# mattduino_uno_v7.net
KiCad netlist of a schematic drawn in EAGLE
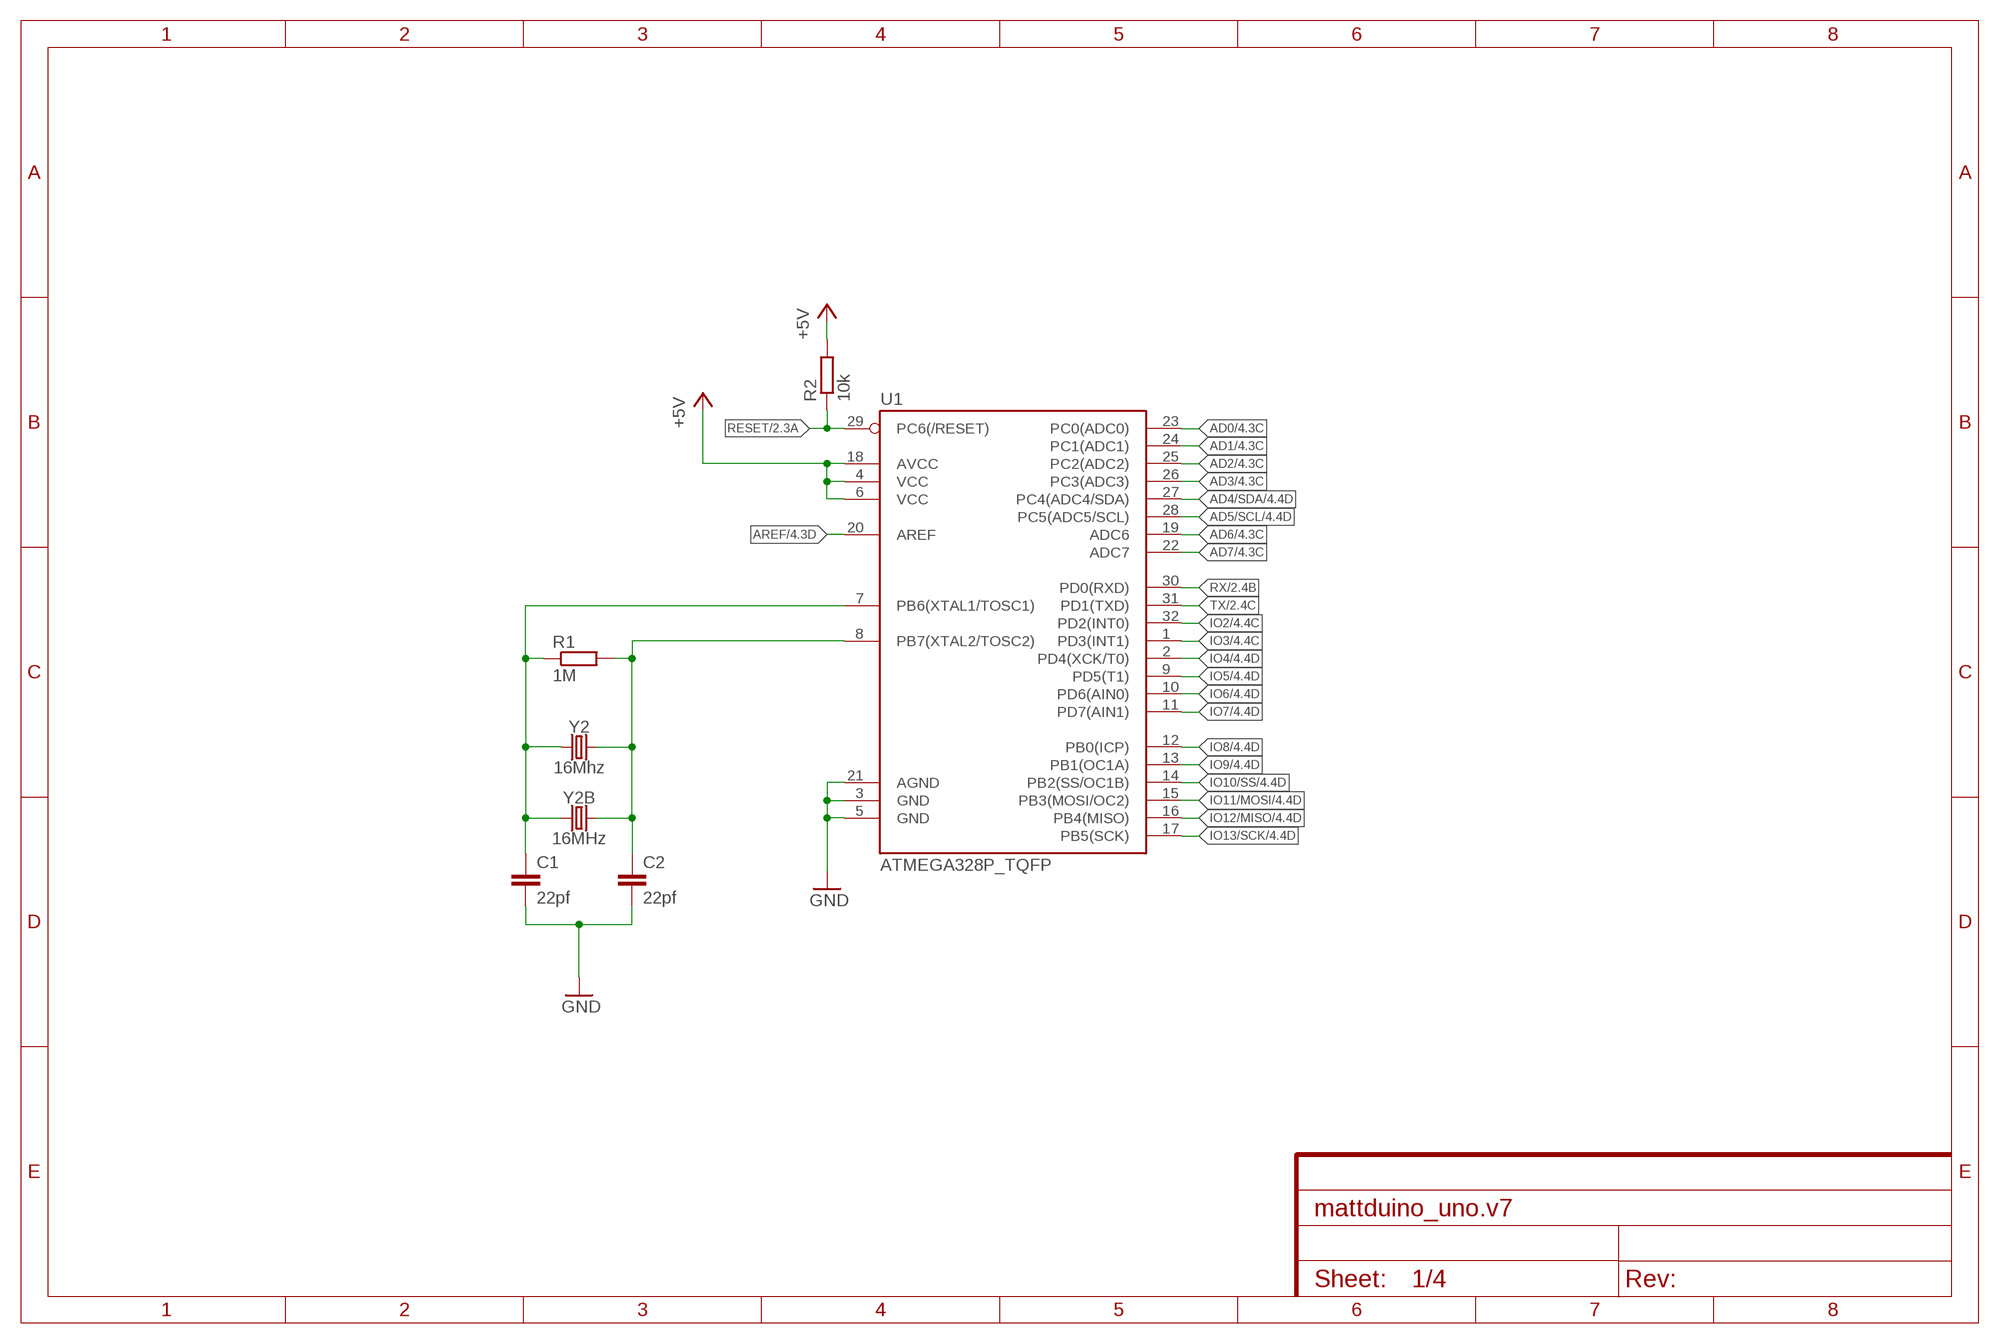
[diagram p0: schematic, sheet 1]
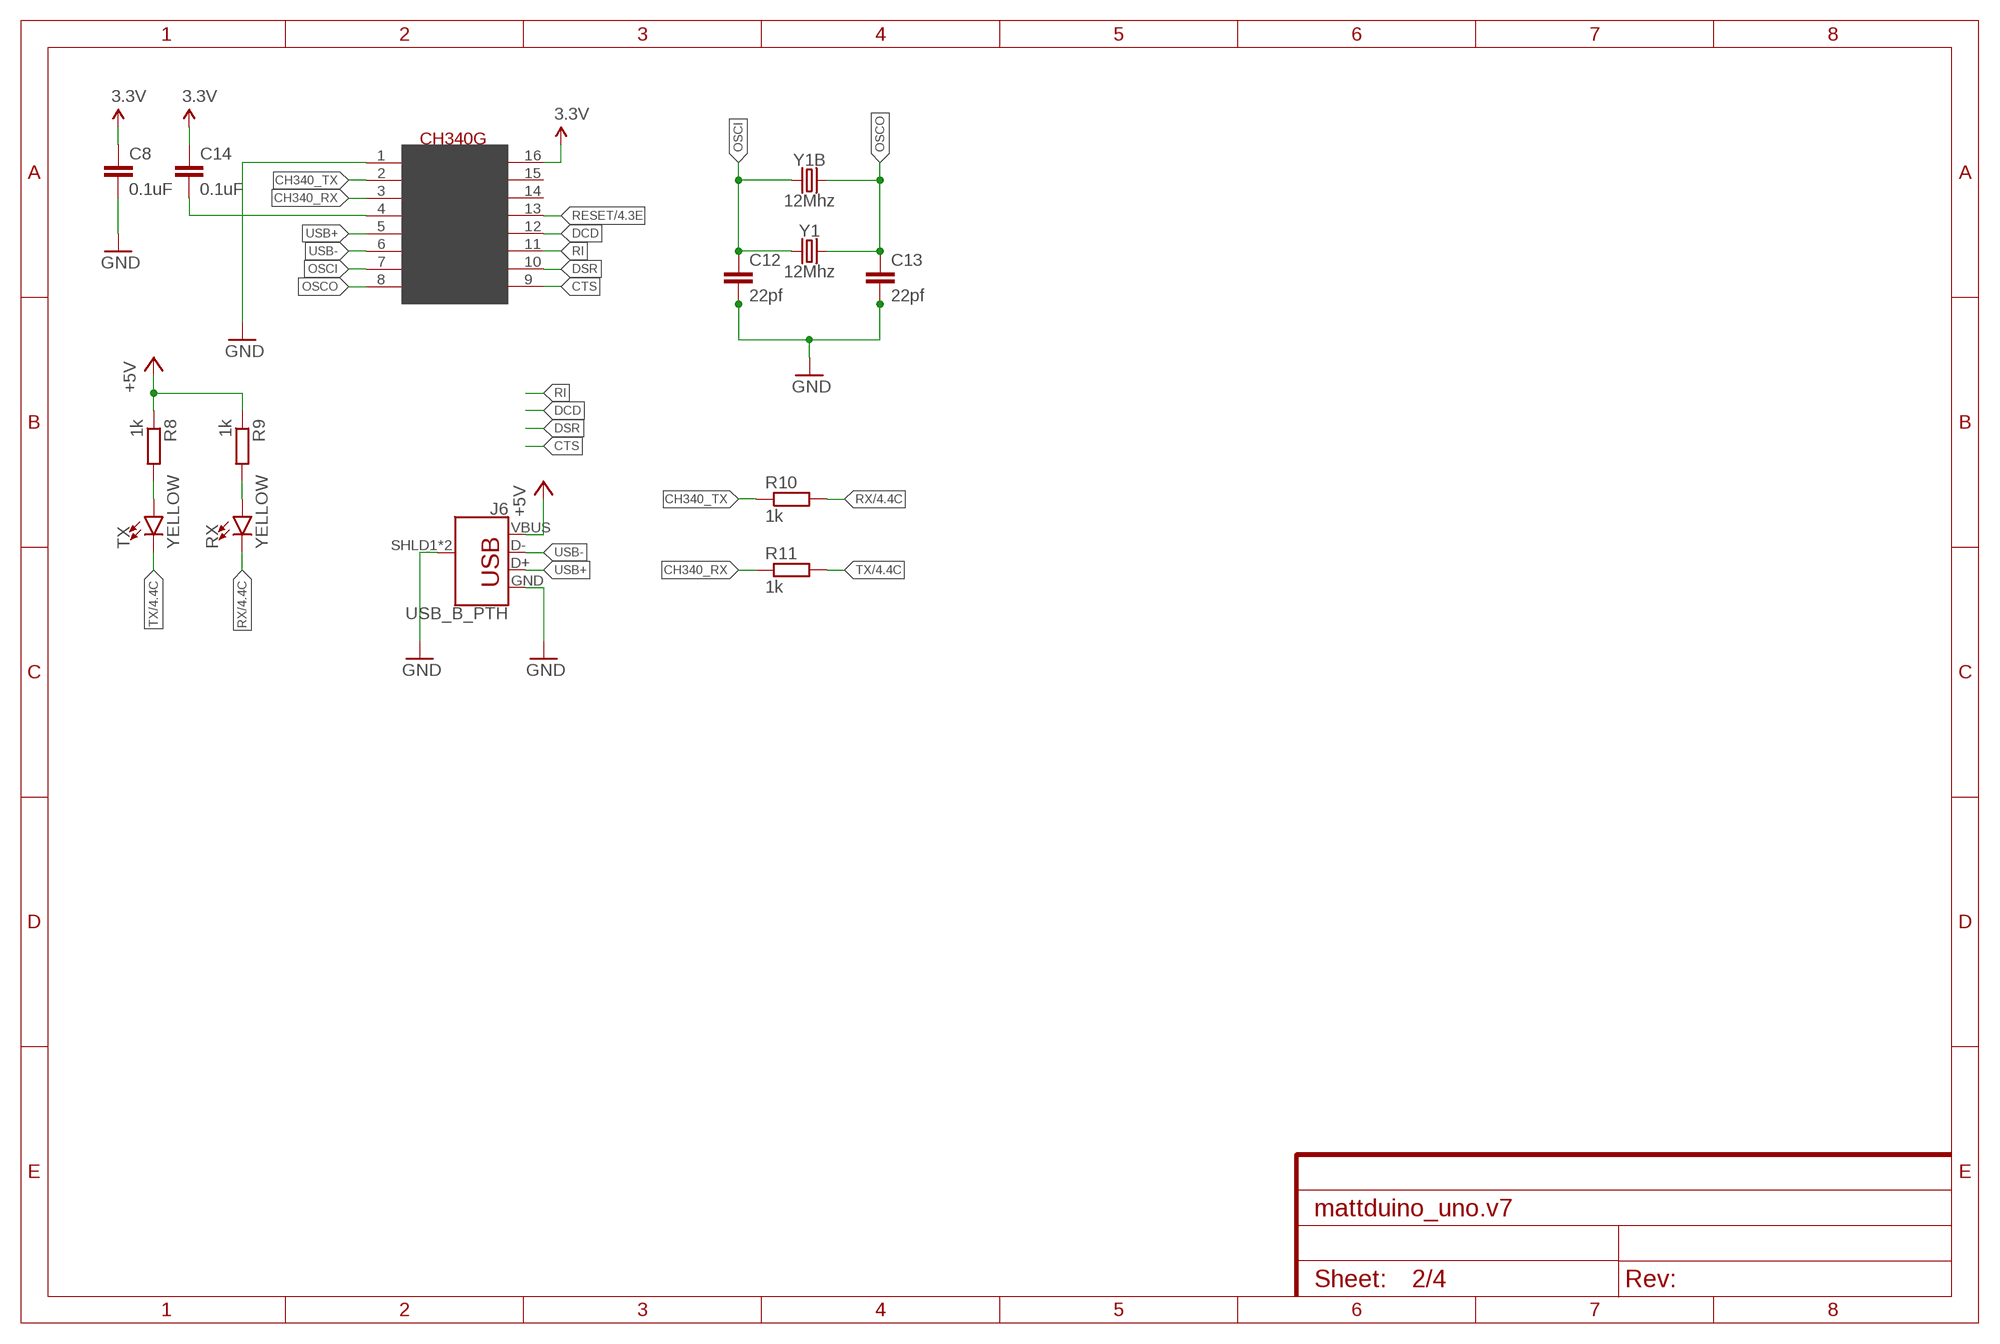
[diagram p1: schematic, sheet 2]
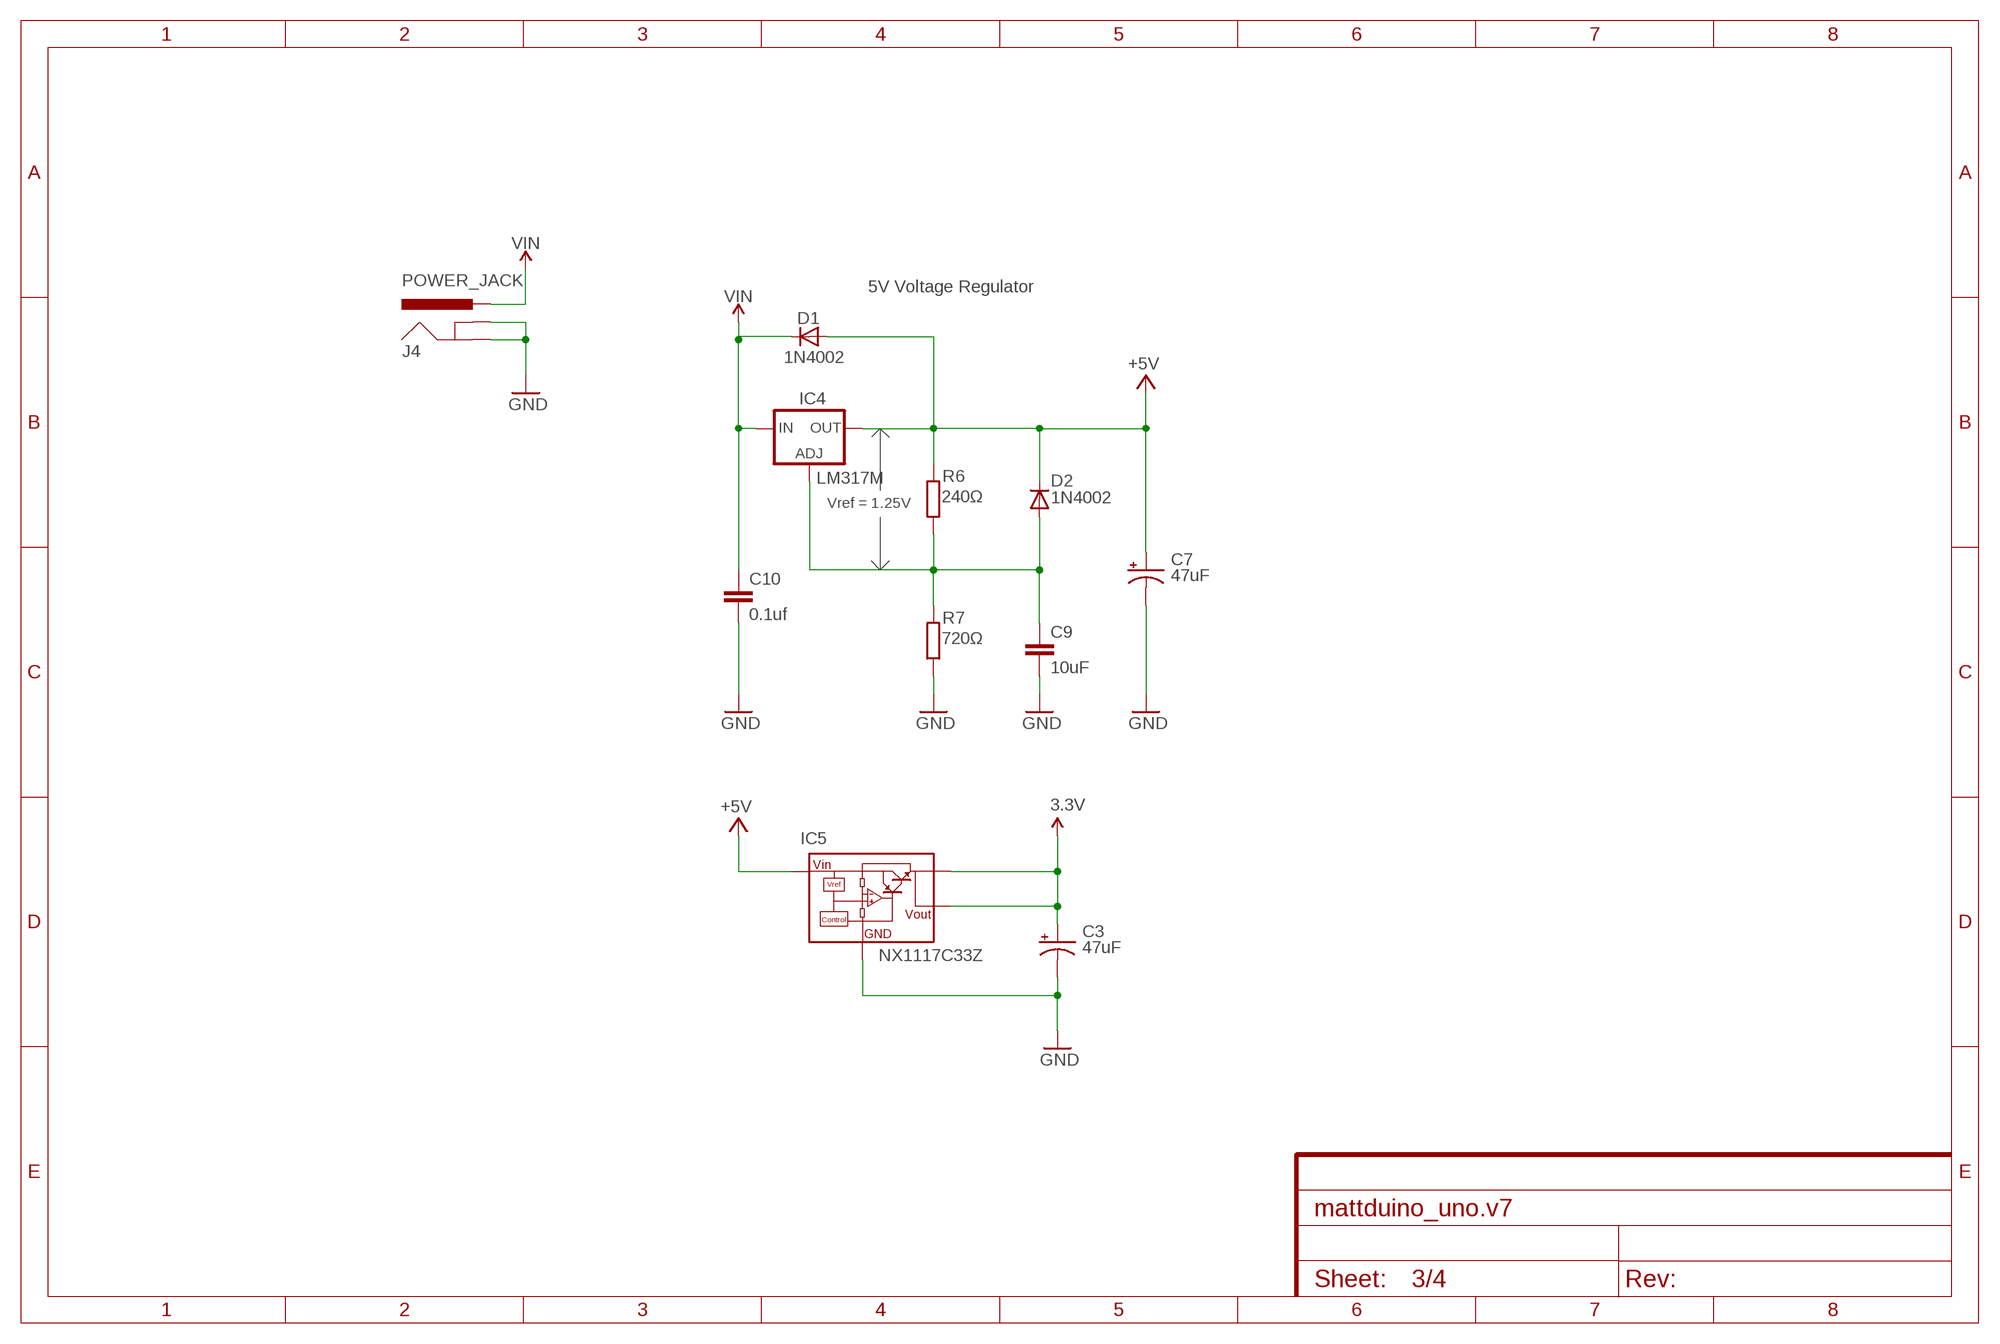
[diagram p2: schematic, sheet 3]
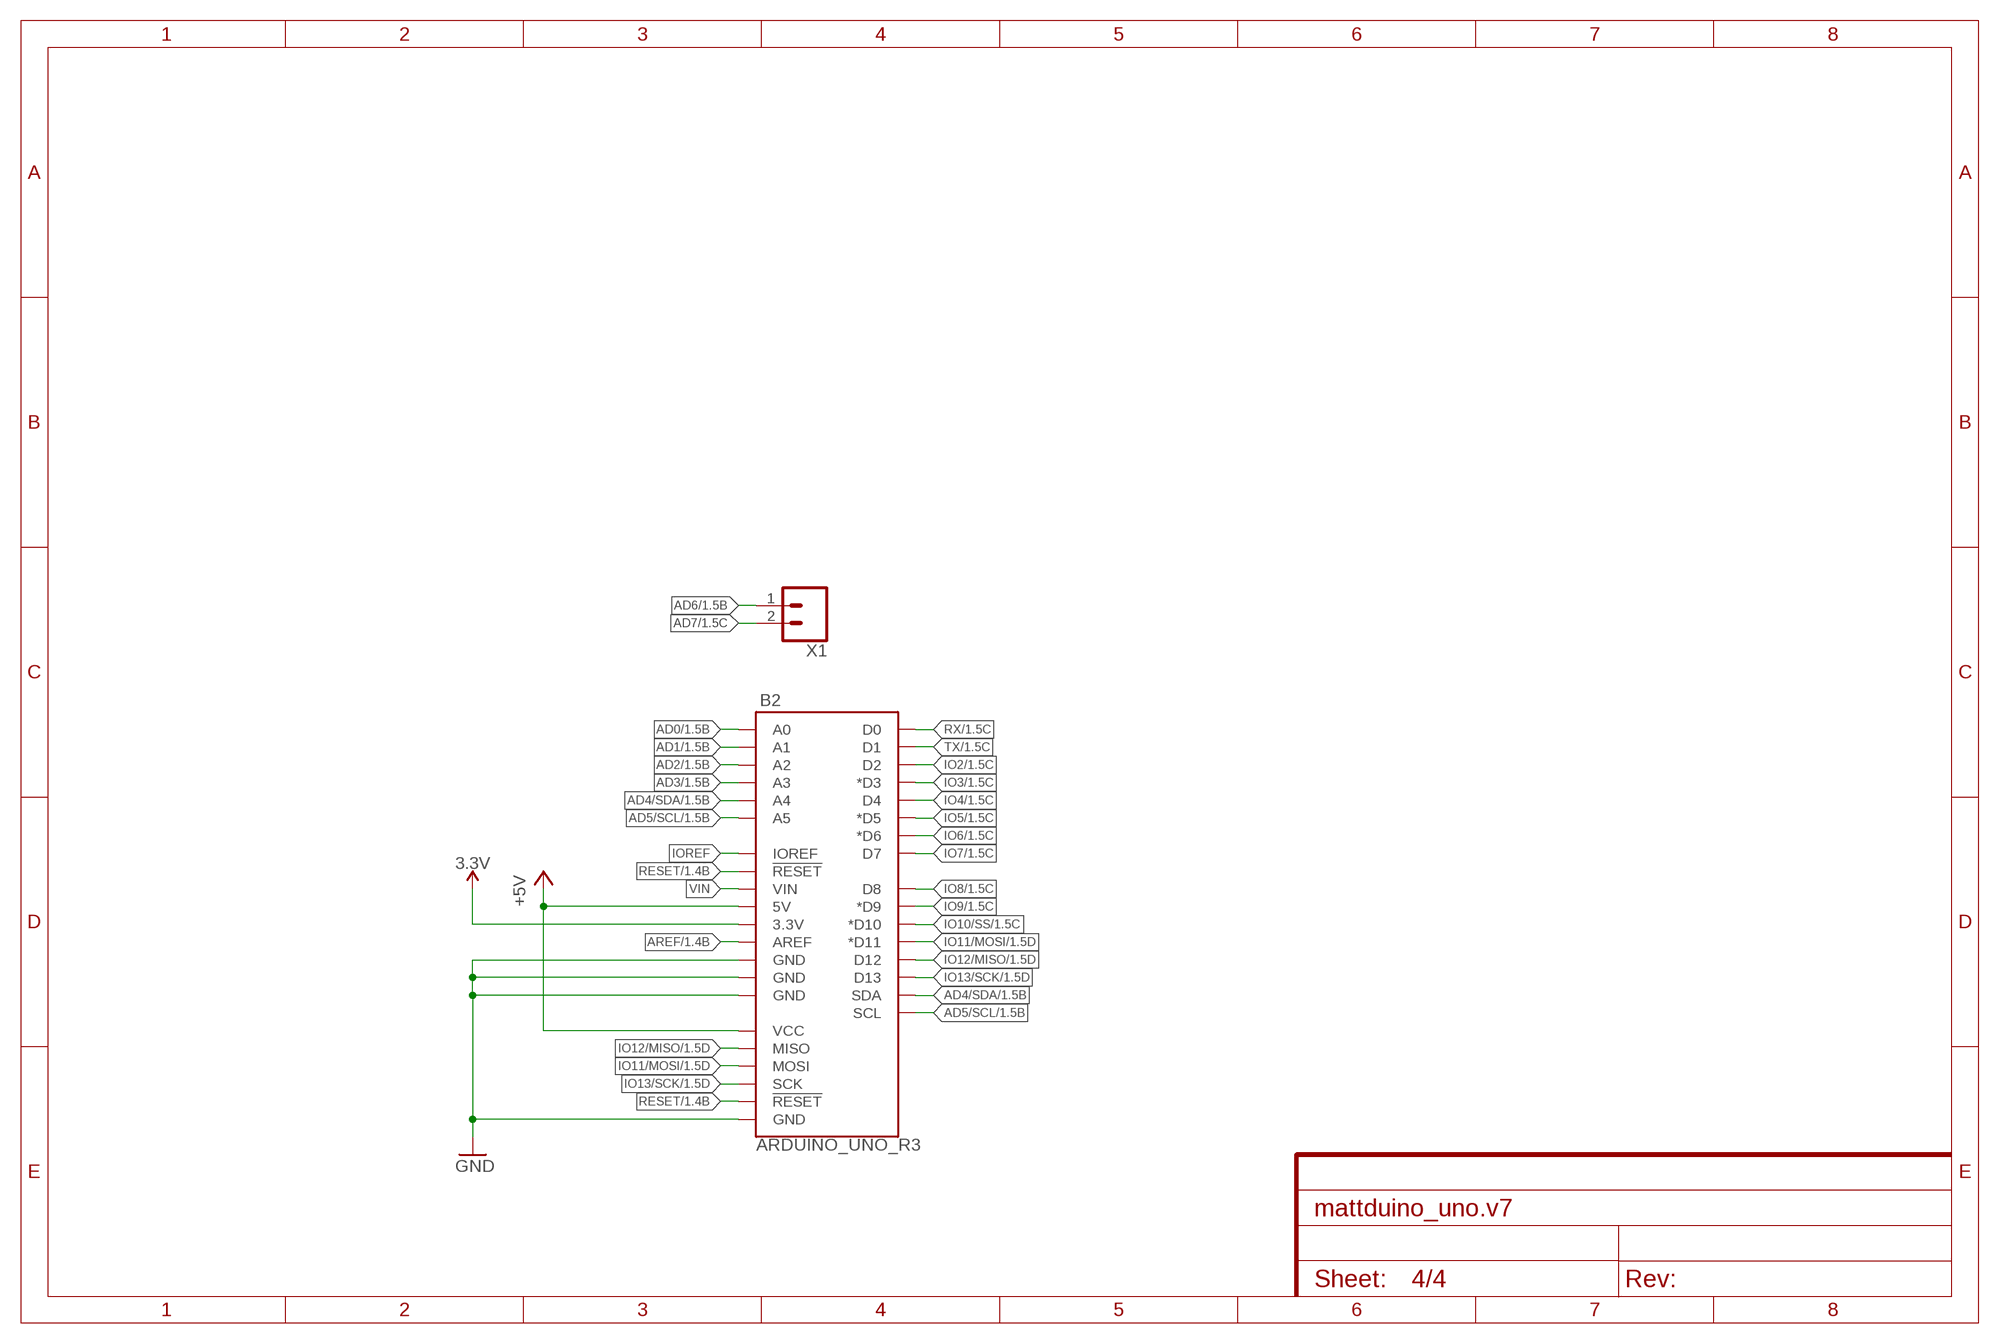
[diagram p3: schematic, sheet 4]

(export (version "E")
  (design (tool "Eeschema 10.0.6"))
  (components
    (comp (ref "C1")
      (value "22pf")
      (footprint "eagle-import:C1206")
      (libsource (lib "eagle-import") (part "C-EUC1206"))
    )
    (comp (ref "C2")
      (value "22pf")
      (footprint "eagle-import:C1206")
      (libsource (lib "eagle-import") (part "C-EUC1206"))
    )
    (comp (ref "R1")
      (value "1M")
      (footprint "eagle-import:R1206")
      (libsource (lib "eagle-import") (part "R-EU_R1206"))
    )
    (comp (ref "R2")
      (value "10k")
      (footprint "eagle-import:R1206")
      (libsource (lib "eagle-import") (part "R-EU_R1206"))
    )
    (comp (ref "U1")
      (value "ATMEGA328P_TQFP")
      (footprint "eagle-import:TQFP32-08")
      (libsource (lib "eagle-import") (part "ATMEGA328P_TQFP"))
    )
    (comp (ref "Y2")
      (value "16Mhz")
      (footprint "eagle-import:HC49UP")
      (libsource (lib "eagle-import") (part "CRYSTAL-8MHZSMD-HC49UP"))
    )
    (comp (ref "Y2B")
      (value "16MHz")
      (footprint "eagle-import:HC49U")
      (libsource (lib "eagle-import") (part "CRYSTALPTH-HC49UV"))
    )
    (comp (ref "C8")
      (value "0.1uF")
      (footprint "eagle-import:C1206")
      (libsource (lib "eagle-import") (part "C-EUC1206"))
    )
    (comp (ref "C12")
      (value "22pf")
      (footprint "eagle-import:C1206")
      (libsource (lib "eagle-import") (part "rcl@1_C-EUC1206"))
    )
    (comp (ref "C13")
      (value "22pf")
      (footprint "eagle-import:C1206")
      (libsource (lib "eagle-import") (part "rcl@1_C-EUC1206"))
    )
    (comp (ref "C14")
      (value "0.1uF")
      (footprint "eagle-import:C1206")
      (libsource (lib "eagle-import") (part "C-EUC1206"))
    )
    (comp (ref "IC3")
      (value "CH340G")
      (footprint "eagle-import:SOIC16")
      (libsource (lib "eagle-import") (part "CH340G"))
    )
    (comp (ref "J6")
      (value "USB_B_PTH")
      (footprint "eagle-import:USB-B-PTH")
      (libsource (lib "eagle-import") (part "USB_B_PTH"))
    )
    (comp (ref "R8")
      (value "1k")
      (footprint "eagle-import:R1206")
      (libsource (lib "eagle-import") (part "R-EU_R1206"))
    )
    (comp (ref "R9")
      (value "1k")
      (footprint "eagle-import:R1206")
      (libsource (lib "eagle-import") (part "R-EU_R1206"))
    )
    (comp (ref "R10")
      (value "1k")
      (footprint "eagle-import:R1206")
      (libsource (lib "eagle-import") (part "R-EU_R1206"))
    )
    (comp (ref "R11")
      (value "1k")
      (footprint "eagle-import:R1206")
      (libsource (lib "eagle-import") (part "R-EU_R1206"))
    )
    (comp (ref "RX")
      (value "YELLOW")
      (footprint "eagle-import:LED-1206")
      (libsource (lib "eagle-import") (part "LED1206"))
    )
    (comp (ref "TX")
      (value "YELLOW")
      (footprint "eagle-import:LED-1206")
      (libsource (lib "eagle-import") (part "LED1206"))
    )
    (comp (ref "Y1")
      (value "12Mhz")
      (footprint "eagle-import:HC49U")
      (libsource (lib "eagle-import") (part "CRYSTALPTH-HC49UV"))
    )
    (comp (ref "Y1B")
      (value "12Mhz")
      (footprint "eagle-import:HC49UP")
      (libsource (lib "eagle-import") (part "CRYSTAL-8MHZSMD-HC49UP"))
    )
    (comp (ref "C3")
      (value "47uF")
      (footprint "eagle-import:PANASONIC_D")
      (libsource (lib "eagle-import") (part "47UF-POLAR-PANASONIC_D-35V-20%"))
    )
    (comp (ref "C7")
      (value "47uF")
      (footprint "eagle-import:PANASONIC_D")
      (libsource (lib "eagle-import") (part "47UF-POLAR-PANASONIC_D-35V-20%"))
    )
    (comp (ref "C9")
      (value "10uF")
      (footprint "eagle-import:C1206")
      (libsource (lib "eagle-import") (part "C-EUC1206"))
    )
    (comp (ref "C10")
      (value "0.1uf")
      (footprint "eagle-import:C1206")
      (libsource (lib "eagle-import") (part "C-EUC1206"))
    )
    (comp (ref "D1")
      (value "1N4002")
      (footprint "eagle-import:SOD-123")
      (libsource (lib "eagle-import") (part "DIODESOD-123"))
    )
    (comp (ref "D2")
      (value "1N4002")
      (footprint "eagle-import:SOD-123")
      (libsource (lib "eagle-import") (part "DIODESOD-123"))
    )
    (comp (ref "IC4")
      (value "LM317MBSTT3")
      (footprint "eagle-import:SOT223")
      (fields (field (name "PARTNUMBER") "LM317M"))
      (libsource (lib "eagle-import") (part "LM317?MBSTT3"))
    )
    (comp (ref "IC5")
      (value "NX1117C33Z")
      (footprint "eagle-import:SOT223")
      (fields (field (name "TOLERANCE") "1.25%") (field (name "VOLTAGE") "5.0V"))
      (libsource (lib "eagle-import") (part "NX1117CZ33"))
    )
    (comp (ref "J4")
      (value "POWER_JACK")
      (footprint "eagle-import:POWER_JACK_PTH")
      (libsource (lib "eagle-import") (part "POWER_JACK"))
    )
    (comp (ref "R6")
      (value "240Ω")
      (footprint "eagle-import:R1206")
      (libsource (lib "eagle-import") (part "R-EU_R1206"))
    )
    (comp (ref "R7")
      (value "720Ω")
      (footprint "eagle-import:R1206")
      (libsource (lib "eagle-import") (part "R-EU_R1206"))
    )
    (comp (ref "B2")
      (value "ARDUINO_UNO_R3")
      (footprint "eagle-import:ARDUINO_R3")
      (libsource (lib "eagle-import") (part "ARDUINO_UNO_R3"))
    )
    (comp (ref "X1")
      (value "CONN_02")
      (footprint "eagle-import:1X02")
      (libsource (lib "eagle-import") (part "CONN_02"))
    )
  )
  (nets
    (net (code "1") (name "+5V") (class "Default")
      (node (ref "B2") (pin "5V") (pinfunction "5V_5V") (pintype "bidirectional"))
      (node (ref "B2") (pin "VCC") (pinfunction "VCC_VCC") (pintype "bidirectional"))
      (node (ref "C7") (pin "+") (pinfunction "+_+") (pintype "passive"))
      (node (ref "D1") (pin "A") (pinfunction "A_A") (pintype "passive"))
      (node (ref "D2") (pin "C") (pinfunction "C_C") (pintype "passive"))
      (node (ref "IC4") (pin "4") (pinfunction "OUT_4") (pintype "passive"))
      (node (ref "IC5") (pin "3") (pinfunction "VIN_3") (pintype "input"))
      (node (ref "J6") (pin "VBUS") (pinfunction "VBUS_VBUS") (pintype "power_in"))
      (node (ref "R2") (pin "2") (pinfunction "2_2") (pintype "passive"))
      (node (ref "R6") (pin "2") (pinfunction "2_2") (pintype "passive"))
      (node (ref "R8") (pin "1") (pinfunction "1_1") (pintype "passive"))
      (node (ref "R9") (pin "1") (pinfunction "1_1") (pintype "passive"))
      (node (ref "U1") (pin "18") (pinfunction "AVCC_18") (pintype "bidirectional"))
      (node (ref "U1") (pin "4") (pinfunction "VCC_4") (pintype "bidirectional"))
      (node (ref "U1") (pin "6") (pinfunction "VCC_6") (pintype "bidirectional"))
    )
    (net (code "2") (name "3.3V") (class "Default")
      (node (ref "B2") (pin "3.3V") (pinfunction "3.3V_3.3V") (pintype "bidirectional"))
      (node (ref "C14") (pin "1") (pinfunction "1_1") (pintype "passive"))
      (node (ref "C3") (pin "+") (pinfunction "+_+") (pintype "passive"))
      (node (ref "C8") (pin "1") (pinfunction "1_1") (pintype "passive"))
      (node (ref "IC3") (pin "16") (pinfunction "VCC_16") (pintype "bidirectional"))
      (node (ref "IC5") (pin "2") (pinfunction "VOUT1_2") (pintype "output"))
      (node (ref "IC5") (pin "4") (pinfunction "VOUT_4") (pintype "output"))
    )
    (net (code "3") (name "AD0") (class "Default")
      (node (ref "B2") (pin "A0") (pinfunction "A0_A0") (pintype "bidirectional"))
      (node (ref "U1") (pin "23") (pinfunction "PC0(ADC0)_23") (pintype "bidirectional"))
    )
    (net (code "4") (name "AD1") (class "Default")
      (node (ref "B2") (pin "A1") (pinfunction "A1_A1") (pintype "bidirectional"))
      (node (ref "U1") (pin "24") (pinfunction "PC1(ADC1)_24") (pintype "bidirectional"))
    )
    (net (code "5") (name "AD2") (class "Default")
      (node (ref "B2") (pin "A2") (pinfunction "A2_A2") (pintype "bidirectional"))
      (node (ref "U1") (pin "25") (pinfunction "PC2(ADC2)_25") (pintype "bidirectional"))
    )
    (net (code "6") (name "AD3") (class "Default")
      (node (ref "B2") (pin "A3") (pinfunction "A3_A3") (pintype "bidirectional"))
      (node (ref "U1") (pin "26") (pinfunction "PC3(ADC3)_26") (pintype "bidirectional"))
    )
    (net (code "7") (name "AD4{slash}SDA") (class "Default")
      (node (ref "B2") (pin "A4") (pinfunction "A4_A4") (pintype "bidirectional"))
      (node (ref "B2") (pin "SDA") (pinfunction "SDA_SDA") (pintype "bidirectional"))
      (node (ref "U1") (pin "27") (pinfunction "PC4(ADC4/SDA)_27") (pintype "bidirectional"))
    )
    (net (code "8") (name "AD5{slash}SCL") (class "Default")
      (node (ref "B2") (pin "A5") (pinfunction "A5_A5") (pintype "bidirectional"))
      (node (ref "B2") (pin "SCL") (pinfunction "SCL_SCL") (pintype "bidirectional"))
      (node (ref "U1") (pin "28") (pinfunction "PC5(ADC5/SCL)_28") (pintype "bidirectional"))
    )
    (net (code "9") (name "AD6") (class "Default")
      (node (ref "U1") (pin "19") (pinfunction "ADC6_19") (pintype "bidirectional"))
      (node (ref "X1") (pin "1") (pinfunction "1_1") (pintype "passive"))
    )
    (net (code "10") (name "AD7") (class "Default")
      (node (ref "U1") (pin "22") (pinfunction "ADC7_22") (pintype "bidirectional"))
      (node (ref "X1") (pin "2") (pinfunction "2_2") (pintype "passive"))
    )
    (net (code "11") (name "AREF") (class "Default")
      (node (ref "B2") (pin "AREF") (pinfunction "AREF_AREF") (pintype "bidirectional"))
      (node (ref "U1") (pin "20") (pinfunction "AREF_20") (pintype "bidirectional"))
    )
    (net (code "12") (name "CH340_RX") (class "Default")
      (node (ref "IC3") (pin "3") (pinfunction "RX_3") (pintype "bidirectional"))
      (node (ref "R11") (pin "1") (pinfunction "1_1") (pintype "passive"))
    )
    (net (code "13") (name "CH340_TX") (class "Default")
      (node (ref "IC3") (pin "2") (pinfunction "TX_2") (pintype "bidirectional"))
      (node (ref "R10") (pin "1") (pinfunction "1_1") (pintype "passive"))
    )
    (net (code "14") (name "CTS") (class "Default")
      (node (ref "IC3") (pin "9") (pinfunction "CTS_9") (pintype "bidirectional"))
    )
    (net (code "15") (name "DCD") (class "Default")
      (node (ref "IC3") (pin "12") (pinfunction "DCD_12") (pintype "bidirectional"))
    )
    (net (code "16") (name "DSR") (class "Default")
      (node (ref "IC3") (pin "10") (pinfunction "DSR_10") (pintype "bidirectional"))
    )
    (net (code "17") (name "GND") (class "Default")
      (node (ref "B2") (pin "GND@1") (pinfunction "GND_GND@1") (pintype "bidirectional"))
      (node (ref "B2") (pin "GND@2") (pinfunction "GND_GND@2") (pintype "bidirectional"))
      (node (ref "B2") (pin "GND@3") (pinfunction "GND_GND@3") (pintype "bidirectional"))
      (node (ref "B2") (pin "GND@4") (pinfunction "GND_GND@4") (pintype "bidirectional"))
      (node (ref "C1") (pin "2") (pinfunction "2_2") (pintype "passive"))
      (node (ref "C10") (pin "2") (pinfunction "2_2") (pintype "passive"))
      (node (ref "C12") (pin "2") (pinfunction "2_2") (pintype "passive"))
      (node (ref "C13") (pin "2") (pinfunction "2_2") (pintype "passive"))
      (node (ref "C2") (pin "2") (pinfunction "2_2") (pintype "passive"))
      (node (ref "C3") (pin "-") (pinfunction "-_-") (pintype "passive"))
      (node (ref "C7") (pin "-") (pinfunction "-_-") (pintype "passive"))
      (node (ref "C8") (pin "2") (pinfunction "2_2") (pintype "passive"))
      (node (ref "C9") (pin "2") (pinfunction "2_2") (pintype "passive"))
      (node (ref "IC3") (pin "1") (pinfunction "GND_1") (pintype "bidirectional"))
      (node (ref "IC5") (pin "1") (pinfunction "GND_1") (pintype "passive"))
      (node (ref "J4") (pin "GND") (pinfunction "GND_GND") (pintype "bidirectional"))
      (node (ref "J4") (pin "GNDBREAK") (pinfunction "GNDBREAK_GNDBREAK") (pintype "bidirectional"))
      (node (ref "J6") (pin "GND") (pinfunction "GND_GND") (pintype "power_in"))
      (node (ref "J6") (pin "SHLD1") (pinfunction "SHIELD_SHLD1") (pintype "bidirectional"))
      (node (ref "J6") (pin "SHLD2") (pinfunction "SHIELD_SHLD2") (pintype "bidirectional"))
      (node (ref "R7") (pin "1") (pinfunction "1_1") (pintype "passive"))
      (node (ref "U1") (pin "21") (pinfunction "AGND_21") (pintype "bidirectional"))
      (node (ref "U1") (pin "3") (pinfunction "GND_3") (pintype "bidirectional"))
      (node (ref "U1") (pin "5") (pinfunction "GND_5") (pintype "bidirectional"))
    )
    (net (code "18") (name "IO2") (class "Default")
      (node (ref "B2") (pin "D2") (pinfunction "D2_D2") (pintype "bidirectional"))
      (node (ref "U1") (pin "32") (pinfunction "PD2(INT0)_32") (pintype "bidirectional"))
    )
    (net (code "19") (name "IO3") (class "Default")
      (node (ref "B2") (pin "D3") (pinfunction "*D3_D3") (pintype "bidirectional"))
      (node (ref "U1") (pin "1") (pinfunction "PD3(INT1)_1") (pintype "bidirectional"))
    )
    (net (code "20") (name "IO4") (class "Default")
      (node (ref "B2") (pin "D4") (pinfunction "D4_D4") (pintype "bidirectional"))
      (node (ref "U1") (pin "2") (pinfunction "PD4(XCK/T0)_2") (pintype "bidirectional"))
    )
    (net (code "21") (name "IO5") (class "Default")
      (node (ref "B2") (pin "D5") (pinfunction "*D5_D5") (pintype "bidirectional"))
      (node (ref "U1") (pin "9") (pinfunction "PD5(T1)_9") (pintype "bidirectional"))
    )
    (net (code "22") (name "IO6") (class "Default")
      (node (ref "B2") (pin "D6") (pinfunction "*D6_D6") (pintype "bidirectional"))
      (node (ref "U1") (pin "10") (pinfunction "PD6(AIN0)_10") (pintype "bidirectional"))
    )
    (net (code "23") (name "IO7") (class "Default")
      (node (ref "B2") (pin "D7") (pinfunction "D7_D7") (pintype "bidirectional"))
      (node (ref "U1") (pin "11") (pinfunction "PD7(AIN1)_11") (pintype "bidirectional"))
    )
    (net (code "24") (name "IO8") (class "Default")
      (node (ref "B2") (pin "D8") (pinfunction "D8_D8") (pintype "bidirectional"))
      (node (ref "U1") (pin "12") (pinfunction "PB0(ICP)_12") (pintype "bidirectional"))
    )
    (net (code "25") (name "IO9") (class "Default")
      (node (ref "B2") (pin "D9") (pinfunction "*D9_D9") (pintype "bidirectional"))
      (node (ref "U1") (pin "13") (pinfunction "PB1(OC1A)_13") (pintype "bidirectional"))
    )
    (net (code "26") (name "IO10{slash}SS") (class "Default")
      (node (ref "B2") (pin "D10") (pinfunction "*D10_D10") (pintype "bidirectional"))
      (node (ref "U1") (pin "14") (pinfunction "PB2(SS/OC1B)_14") (pintype "bidirectional"))
    )
    (net (code "27") (name "IO11{slash}MOSI") (class "Default")
      (node (ref "B2") (pin "D11") (pinfunction "*D11_D11") (pintype "bidirectional"))
      (node (ref "B2") (pin "MOSI") (pinfunction "MOSI_MOSI") (pintype "bidirectional"))
      (node (ref "U1") (pin "15") (pinfunction "PB3(MOSI/OC2)_15") (pintype "bidirectional"))
    )
    (net (code "28") (name "IO12{slash}MISO") (class "Default")
      (node (ref "B2") (pin "D12") (pinfunction "D12_D12") (pintype "bidirectional"))
      (node (ref "B2") (pin "MISO") (pinfunction "MISO_MISO") (pintype "bidirectional"))
      (node (ref "U1") (pin "16") (pinfunction "PB4(MISO)_16") (pintype "bidirectional"))
    )
    (net (code "29") (name "IO13{slash}SCK") (class "Default")
      (node (ref "B2") (pin "D13") (pinfunction "D13_D13") (pintype "bidirectional"))
      (node (ref "B2") (pin "SCK") (pinfunction "SCK_SCK") (pintype "bidirectional"))
      (node (ref "U1") (pin "17") (pinfunction "PB5(SCK)_17") (pintype "bidirectional"))
    )
    (net (code "30") (name "IOREF") (class "Default")
      (node (ref "B2") (pin "IOREF") (pinfunction "IOREF_IOREF") (pintype "bidirectional"))
    )
    (net (code "31") (name "Net-(IC3-V3)") (class "Default")
      (node (ref "C14") (pin "2") (pinfunction "2_2") (pintype "passive"))
      (node (ref "IC3") (pin "4") (pinfunction "V3_4") (pintype "bidirectional"))
    )
    (net (code "32") (name "Net-(IC4-ADJ)") (class "Default")
      (node (ref "C9") (pin "1") (pinfunction "1_1") (pintype "passive"))
      (node (ref "D2") (pin "A") (pinfunction "A_A") (pintype "passive"))
      (node (ref "IC4") (pin "1") (pinfunction "ADJ_1") (pintype "input"))
      (node (ref "R6") (pin "1") (pinfunction "1_1") (pintype "passive"))
      (node (ref "R7") (pin "2") (pinfunction "2_2") (pintype "passive"))
    )
    (net (code "33") (name "Net-(R8-Pad2)") (class "Default")
      (node (ref "R8") (pin "2") (pinfunction "2_2") (pintype "passive"))
      (node (ref "TX") (pin "A") (pinfunction "A_A") (pintype "passive"))
    )
    (net (code "34") (name "Net-(R9-Pad2)") (class "Default")
      (node (ref "R9") (pin "2") (pinfunction "2_2") (pintype "passive"))
      (node (ref "RX") (pin "A") (pinfunction "A_A") (pintype "passive"))
    )
    (net (code "35") (name "Net-(U1-PB6(XTAL1{slash}TOSC1))") (class "Default")
      (node (ref "C1") (pin "1") (pinfunction "1_1") (pintype "passive"))
      (node (ref "R1") (pin "1") (pinfunction "1_1") (pintype "passive"))
      (node (ref "U1") (pin "7") (pinfunction "PB6(XTAL1/TOSC1)_7") (pintype "bidirectional"))
      (node (ref "Y2") (pin "1") (pinfunction "1_1") (pintype "passive"))
      (node (ref "Y2B") (pin "1") (pinfunction "1_1") (pintype "passive"))
    )
    (net (code "36") (name "Net-(U1-PB7(XTAL2{slash}TOSC2))") (class "Default")
      (node (ref "C2") (pin "1") (pinfunction "1_1") (pintype "passive"))
      (node (ref "R1") (pin "2") (pinfunction "2_2") (pintype "passive"))
      (node (ref "U1") (pin "8") (pinfunction "PB7(XTAL2/TOSC2)_8") (pintype "bidirectional"))
      (node (ref "Y2") (pin "2") (pinfunction "2_2") (pintype "passive"))
      (node (ref "Y2B") (pin "2") (pinfunction "2_2") (pintype "passive"))
    )
    (net (code "37") (name "OSCI") (class "Default")
      (node (ref "C12") (pin "1") (pinfunction "1_1") (pintype "passive"))
      (node (ref "IC3") (pin "7") (pinfunction "XI_7") (pintype "bidirectional"))
      (node (ref "Y1") (pin "1") (pinfunction "1_1") (pintype "passive"))
      (node (ref "Y1B") (pin "1") (pinfunction "1_1") (pintype "passive"))
    )
    (net (code "38") (name "OSCO") (class "Default")
      (node (ref "C13") (pin "1") (pinfunction "1_1") (pintype "passive"))
      (node (ref "IC3") (pin "8") (pinfunction "XO_8") (pintype "bidirectional"))
      (node (ref "Y1") (pin "2") (pinfunction "2_2") (pintype "passive"))
      (node (ref "Y1B") (pin "2") (pinfunction "2_2") (pintype "passive"))
    )
    (net (code "39") (name "RESET") (class "Default")
      (node (ref "B2") (pin "RESET@1") (pinfunction "~{RESET}_RESET@1") (pintype "bidirectional"))
      (node (ref "B2") (pin "RESET@2") (pinfunction "~{RESET}_RESET@2") (pintype "bidirectional"))
      (node (ref "IC3") (pin "13") (pinfunction "DTR_13") (pintype "bidirectional"))
      (node (ref "R2") (pin "1") (pinfunction "1_1") (pintype "passive"))
      (node (ref "U1") (pin "29") (pinfunction "PC6(/RESET)_29") (pintype "bidirectional"))
    )
    (net (code "40") (name "RI") (class "Default")
      (node (ref "IC3") (pin "11") (pinfunction "RI_11") (pintype "bidirectional"))
    )
    (net (code "41") (name "RX") (class "Default")
      (node (ref "B2") (pin "D0") (pinfunction "D0_D0") (pintype "bidirectional"))
      (node (ref "R10") (pin "2") (pinfunction "2_2") (pintype "passive"))
      (node (ref "RX") (pin "C") (pinfunction "C_C") (pintype "passive"))
      (node (ref "U1") (pin "30") (pinfunction "PD0(RXD)_30") (pintype "bidirectional"))
    )
    (net (code "42") (name "TX") (class "Default")
      (node (ref "B2") (pin "D1") (pinfunction "D1_D1") (pintype "bidirectional"))
      (node (ref "R11") (pin "2") (pinfunction "2_2") (pintype "passive"))
      (node (ref "TX") (pin "C") (pinfunction "C_C") (pintype "passive"))
      (node (ref "U1") (pin "31") (pinfunction "PD1(TXD)_31") (pintype "bidirectional"))
    )
    (net (code "43") (name "USB+") (class "Default")
      (node (ref "IC3") (pin "5") (pinfunction "D+_5") (pintype "bidirectional"))
      (node (ref "J6") (pin "D+") (pinfunction "D+_D+") (pintype "bidirectional"))
    )
    (net (code "44") (name "USB-") (class "Default")
      (node (ref "IC3") (pin "6") (pinfunction "D-_6") (pintype "bidirectional"))
      (node (ref "J6") (pin "D-") (pinfunction "D-_D-") (pintype "bidirectional"))
    )
    (net (code "45") (name "VIN") (class "Default")
      (node (ref "B2") (pin "VIN") (pinfunction "VIN_VIN") (pintype "bidirectional"))
      (node (ref "C10") (pin "1") (pinfunction "1_1") (pintype "passive"))
      (node (ref "D1") (pin "C") (pinfunction "C_C") (pintype "passive"))
      (node (ref "IC4") (pin "3") (pinfunction "IN_3") (pintype "input"))
      (node (ref "J4") (pin "PWR") (pinfunction "PWR_PWR") (pintype "bidirectional"))
    )
    (net (code "46") (name "unconnected-(IC3-RS232-Pad15)") (class "Default")
      (node (ref "IC3") (pin "15") (pinfunction "RS232_15") (pintype "bidirectional"))
    )
    (net (code "47") (name "unconnected-(IC3-RTS-Pad14)") (class "Default")
      (node (ref "IC3") (pin "14") (pinfunction "RTS_14") (pintype "bidirectional"))
    )
  )
)
